# CAN.net
KiCad netlist of a schematic drawn in Altium Designer
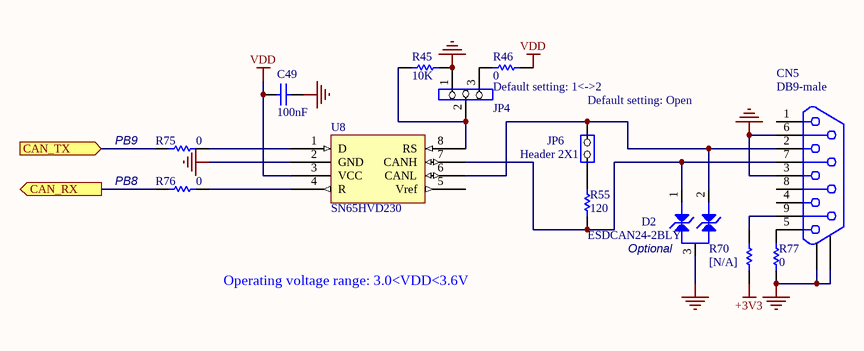
[diagram p0: CAN.SchDoc]

(export (version "E")
  (design (tool "Eeschema 10.0.6"))
  (components
    (comp (ref "C49")
      (value "100nF")
      (footprint "0402C")
      (description "Capacitor")
      (fields (field (name "PUBLISHER") "Altium Limited"))
      (libsource (lib "Miscellaneous Devices") (part "CAP"))
    )
    (comp (ref "CN5") (value "DB9-male") (footprint "DB9/M") (libsource (lib "MB1070") (part "DB9")))
    (comp (ref "D2")
      (value "ESDCAN24-2BLY")
      (footprint "SOT23-213")
      (libsource (lib "mb1045") (part "ESDCAN24-2BLY"))
    )
    (comp (ref "JP4")
      (value "Header 3X1")
      (footprint "SIP3")
      (libsource (lib "STR910_SCHLIB") (part "Jumper3"))
    )
    (comp (ref "JP6") (value "Header 2X1") (footprint "SIP2") (libsource (lib "*") (part "JP2")))
    (comp (ref "R45")
      (value "10K")
      (footprint "0402R")
      (description "Resistor")
      (fields (field (name "PUBLISHER") "Altium Limited"))
      (libsource (lib "Miscellaneous Devices") (part "res1"))
    )
    (comp (ref "R46")
      (value "0")
      (footprint "0603R")
      (description "Resistor")
      (fields (field (name "PUBLISHER") "Altium Limited"))
      (libsource (lib "Miscellaneous Devices") (part "res1"))
    )
    (comp (ref "R55")
      (value "120")
      (footprint "0402R")
      (description "Resistor")
      (fields (field (name "PUBLISHER") "Altium Limited"))
      (libsource (lib "Miscellaneous Devices") (part "res1"))
    )
    (comp (ref "R70")
      (value "[N/A]")
      (footprint "0603R")
      (description "Resistor")
      (fields (field (name "PUBLISHER") "Altium Limited"))
      (libsource (lib "Miscellaneous Devices") (part "res1"))
    )
    (comp (ref "R75")
      (value "0")
      (footprint "0603R")
      (description "Resistor")
      (fields (field (name "PUBLISHER") "Altium Limited"))
      (libsource (lib "Miscellaneous Devices") (part "Res1"))
    )
    (comp (ref "R76")
      (value "0")
      (footprint "0603R")
      (description "Resistor")
      (fields (field (name "PUBLISHER") "Altium Limited"))
      (libsource (lib "Miscellaneous Devices") (part "Res1"))
    )
    (comp (ref "R77")
      (value "0")
      (footprint "0603R")
      (description "Resistor")
      (fields (field (name "PUBLISHER") "Altium Limited"))
      (libsource (lib "Miscellaneous Devices") (part "res1"))
    )
    (comp (ref "U8")
      (value "SN65HVD230")
      (footprint "SOIC8_1R27_4R9X6")
      (libsource (lib "STR910_SCHLIB") (part "SN65HVD230D"))
    )
  )
  (nets
    (net (code "1") (name "+3V3") (class "Default")
      (node (ref "R70") (pin "1") (pinfunction "1_1") (pintype "passive"))
    )
    (net (code "2") (name "/CAN_RX") (class "Default")
      (node (ref "R76") (pin "1") (pinfunction "1_1") (pintype "passive"))
    )
    (net (code "3") (name "/CAN_TX") (class "Default")
      (node (ref "R75") (pin "2") (pinfunction "2_2") (pintype "passive"))
    )
    (net (code "4") (name "GND") (class "Default")
      (node (ref "C49") (pin "1") (pinfunction "1_1") (pintype "passive"))
      (node (ref "CN5") (pin "10") (pinfunction "10_10") (pintype "passive"))
      (node (ref "CN5") (pin "11") (pinfunction "11_11") (pintype "passive"))
      (node (ref "CN5") (pin "3") (pinfunction "3_3") (pintype "passive"))
      (node (ref "CN5") (pin "6") (pinfunction "6_6") (pintype "passive"))
      (node (ref "D2") (pin "3") (pinfunction "3_3") (pintype "passive"))
      (node (ref "JP4") (pin "1") (pintype "passive"))
      (node (ref "R45") (pin "2") (pinfunction "2_2") (pintype "passive"))
      (node (ref "R77") (pin "1") (pinfunction "1_1") (pintype "passive"))
      (node (ref "U8") (pin "2") (pinfunction "GND_2") (pintype "power_in"))
    )
    (net (code "5") (name "Net-(CN5-Pad5)") (class "Default")
      (node (ref "CN5") (pin "5") (pinfunction "5_5") (pintype "passive"))
      (node (ref "R77") (pin "2") (pinfunction "2_2") (pintype "passive"))
    )
    (net (code "6") (name "Net-(CN5-Pad9)") (class "Default")
      (node (ref "CN5") (pin "9") (pinfunction "9_9") (pintype "passive"))
      (node (ref "R70") (pin "2") (pinfunction "2_2") (pintype "passive"))
    )
    (net (code "7") (name "Net-(JP4-Pad3)") (class "Default")
      (node (ref "JP4") (pin "3") (pintype "passive"))
      (node (ref "R46") (pin "1") (pinfunction "1_1") (pintype "passive"))
    )
    (net (code "8") (name "Net-(JP6-COMMON)") (class "Default")
      (node (ref "JP6") (pin "1") (pinfunction "COMMON_1") (pintype "passive"))
      (node (ref "R55") (pin "2") (pinfunction "2_2") (pintype "passive"))
    )
    (net (code "9") (name "Net-(JP6-NO)") (class "Default")
      (node (ref "CN5") (pin "2") (pinfunction "2_2") (pintype "passive"))
      (node (ref "D2") (pin "2") (pinfunction "2_2") (pintype "passive"))
      (node (ref "JP6") (pin "2") (pinfunction "NO_2") (pintype "passive"))
      (node (ref "U8") (pin "6") (pinfunction "CANL_6") (pintype "bidirectional"))
    )
    (net (code "10") (name "Net-(U8-CANH)") (class "Default")
      (node (ref "CN5") (pin "7") (pinfunction "7_7") (pintype "passive"))
      (node (ref "D2") (pin "1") (pinfunction "1_1") (pintype "passive"))
      (node (ref "R55") (pin "1") (pinfunction "1_1") (pintype "passive"))
      (node (ref "U8") (pin "7") (pinfunction "CANH_7") (pintype "bidirectional"))
    )
    (net (code "11") (name "Net-(U8-D)") (class "Default")
      (node (ref "R75") (pin "1") (pinfunction "1_1") (pintype "passive"))
      (node (ref "U8") (pin "1") (pinfunction "D_1") (pintype "input"))
    )
    (net (code "12") (name "Net-(U8-R)") (class "Default")
      (node (ref "R76") (pin "2") (pinfunction "2_2") (pintype "passive"))
      (node (ref "U8") (pin "4") (pinfunction "R_4") (pintype "output"))
    )
    (net (code "13") (name "Net-(U8-RS)") (class "Default")
      (node (ref "JP4") (pin "2") (pintype "passive"))
      (node (ref "R45") (pin "1") (pinfunction "1_1") (pintype "passive"))
      (node (ref "U8") (pin "8") (pinfunction "RS_8") (pintype "input"))
    )
    (net (code "14") (name "VDD") (class "Default")
      (node (ref "C49") (pin "2") (pinfunction "2_2") (pintype "passive"))
      (node (ref "R46") (pin "2") (pinfunction "2_2") (pintype "passive"))
      (node (ref "U8") (pin "3") (pinfunction "VCC_3") (pintype "power_in"))
    )
    (net (code "15") (name "unconnected-(CN5-Pad1)") (class "Default")
      (node (ref "CN5") (pin "1") (pinfunction "1_1") (pintype "passive"))
    )
    (net (code "16") (name "unconnected-(CN5-Pad4)") (class "Default")
      (node (ref "CN5") (pin "4") (pinfunction "4_4") (pintype "passive"))
    )
    (net (code "17") (name "unconnected-(CN5-Pad8)") (class "Default")
      (node (ref "CN5") (pin "8") (pinfunction "8_8") (pintype "passive"))
    )
    (net (code "18") (name "unconnected-(U8-Vref-Pad5)") (class "Default")
      (node (ref "U8") (pin "5") (pinfunction "Vref_5") (pintype "output"))
    )
  )
)
